# Connector.net
KiCad netlist of a schematic drawn in Altium Designer
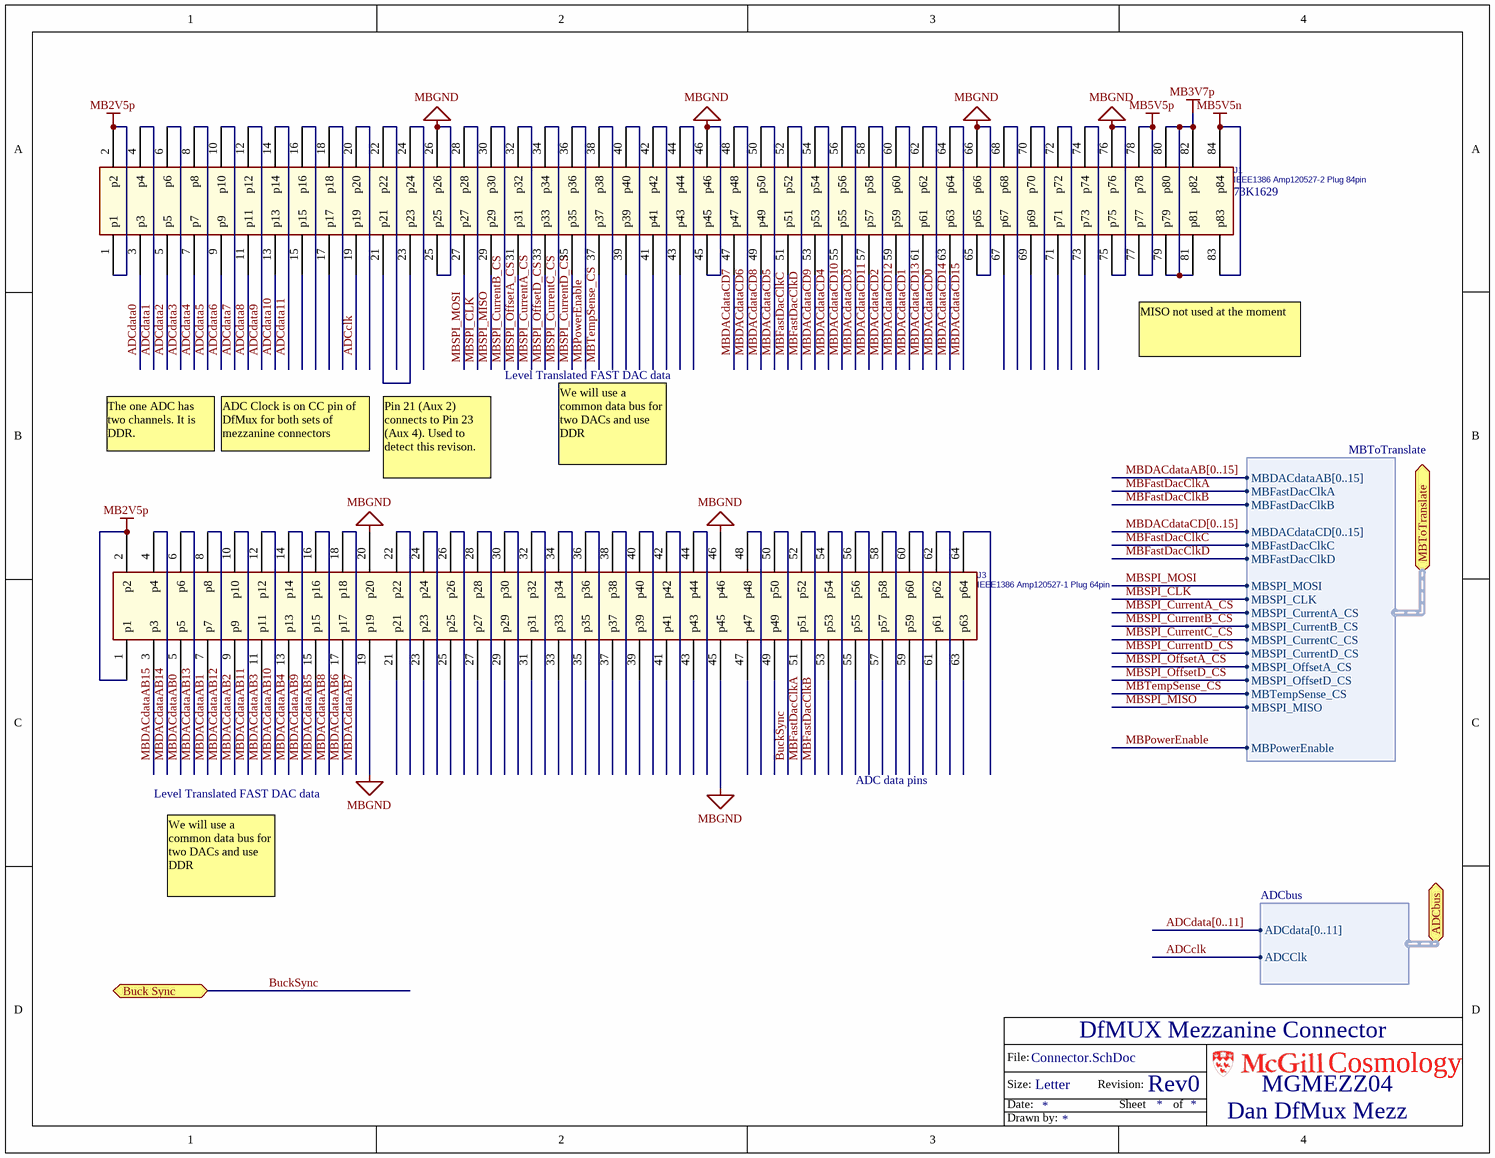
[diagram p0: Connector.SchDoc]

(export (version "E")
  (design (tool "Eeschema 10.0.6"))
  (components
    (comp (ref "J1")
      (value "IEEE1386 Amp120527-2 Plug 84pin")
      (fields
        (field (name "MANUFACTURER") "TE CONNECTIVITY / AMP")
        (field (name "SUPPLIER PART NUMBER 1") "73K1629")
        (field (name "MANUFACTURERS PART NUMBER") "5120527-2")
      )
      (libsource (lib "MGMEZZ04") (part "IEEE1386 Amp120527-2 Plug84pin"))
    )
    (comp (ref "J3")
      (value "IEEE1386 Amp120527-1 Plug 64pin")
      (fields
        (field (name "MANUFACTURER") "TE Connectivity")
        (field (name "MANUFACTURERS PART NUMBER") "120527-1")
      )
      (libsource (lib "MGMEZZ04") (part "IEEE1386 Amp120527-1 Plug 64pin"))
    )
  )
  (nets
    (net (code "4") (name "/ADCclk") (class "Default")
      (node (ref "J1") (pin "19") (pinfunction "p19_19") (pintype "passive"))
    )
    (net (code "5") (name "/ADCdata0") (class "Default")
      (node (ref "J1") (pin "3") (pinfunction "p3_3") (pintype "passive"))
    )
    (net (code "6") (name "/ADCdata1") (class "Default")
      (node (ref "J1") (pin "4") (pinfunction "p4_4") (pintype "passive"))
    )
    (net (code "7") (name "/ADCdata2") (class "Default")
      (node (ref "J1") (pin "5") (pinfunction "p5_5") (pintype "passive"))
    )
    (net (code "8") (name "/ADCdata3") (class "Default")
      (node (ref "J1") (pin "6") (pinfunction "p6_6") (pintype "passive"))
    )
    (net (code "9") (name "/ADCdata4") (class "Default")
      (node (ref "J1") (pin "7") (pinfunction "p7_7") (pintype "passive"))
    )
    (net (code "10") (name "/ADCdata5") (class "Default")
      (node (ref "J1") (pin "8") (pinfunction "p8_8") (pintype "passive"))
    )
    (net (code "11") (name "/ADCdata6") (class "Default")
      (node (ref "J1") (pin "9") (pinfunction "p9_9") (pintype "passive"))
    )
    (net (code "12") (name "/ADCdata7") (class "Default")
      (node (ref "J1") (pin "10") (pinfunction "p10_10") (pintype "passive"))
    )
    (net (code "13") (name "/ADCdata8") (class "Default")
      (node (ref "J1") (pin "11") (pinfunction "p11_11") (pintype "passive"))
    )
    (net (code "14") (name "/ADCdata9") (class "Default")
      (node (ref "J1") (pin "12") (pinfunction "p12_12") (pintype "passive"))
    )
    (net (code "15") (name "/ADCdata10") (class "Default")
      (node (ref "J1") (pin "13") (pinfunction "p13_13") (pintype "passive"))
    )
    (net (code "16") (name "/ADCdata11") (class "Default")
      (node (ref "J1") (pin "14") (pinfunction "p14_14") (pintype "passive"))
    )
    (net (code "17") (name "/BuckSync") (class "Default")
      (node (ref "J3") (pin "50") (pinfunction "p50_50") (pintype "passive"))
    )
    (net (code "18") (name "/MBDACdataAB0") (class "Default")
      (node (ref "J3") (pin "5") (pinfunction "p5_5") (pintype "passive"))
    )
    (net (code "19") (name "/MBDACdataAB1") (class "Default")
      (node (ref "J3") (pin "7") (pinfunction "p7_7") (pintype "passive"))
    )
    (net (code "20") (name "/MBDACdataAB2") (class "Default")
      (node (ref "J3") (pin "9") (pinfunction "p9_9") (pintype "passive"))
    )
    (net (code "21") (name "/MBDACdataAB3") (class "Default")
      (node (ref "J3") (pin "11") (pinfunction "p11_11") (pintype "passive"))
    )
    (net (code "22") (name "/MBDACdataAB4") (class "Default")
      (node (ref "J3") (pin "13") (pinfunction "p13_13") (pintype "passive"))
    )
    (net (code "23") (name "/MBDACdataAB5") (class "Default")
      (node (ref "J3") (pin "15") (pinfunction "p15_15") (pintype "passive"))
    )
    (net (code "24") (name "/MBDACdataAB6") (class "Default")
      (node (ref "J3") (pin "17") (pinfunction "p17_17") (pintype "passive"))
    )
    (net (code "25") (name "/MBDACdataAB7") (class "Default")
      (node (ref "J3") (pin "18") (pinfunction "p18_18") (pintype "passive"))
    )
    (net (code "26") (name "/MBDACdataAB8") (class "Default")
      (node (ref "J3") (pin "16") (pinfunction "p16_16") (pintype "passive"))
    )
    (net (code "27") (name "/MBDACdataAB9") (class "Default")
      (node (ref "J3") (pin "14") (pinfunction "p14_14") (pintype "passive"))
    )
    (net (code "28") (name "/MBDACdataAB10") (class "Default")
      (node (ref "J3") (pin "12") (pinfunction "p12_12") (pintype "passive"))
    )
    (net (code "29") (name "/MBDACdataAB11") (class "Default")
      (node (ref "J3") (pin "10") (pinfunction "p10_10") (pintype "passive"))
    )
    (net (code "30") (name "/MBDACdataAB12") (class "Default")
      (node (ref "J3") (pin "8") (pinfunction "p8_8") (pintype "passive"))
    )
    (net (code "31") (name "/MBDACdataAB13") (class "Default")
      (node (ref "J3") (pin "6") (pinfunction "p6_6") (pintype "passive"))
    )
    (net (code "32") (name "/MBDACdataAB14") (class "Default")
      (node (ref "J3") (pin "4") (pinfunction "p4_4") (pintype "passive"))
    )
    (net (code "33") (name "/MBDACdataAB15") (class "Default")
      (node (ref "J3") (pin "3") (pinfunction "p3_3") (pintype "passive"))
    )
    (net (code "35") (name "/MBDACdataCD0") (class "Default")
      (node (ref "J1") (pin "62") (pinfunction "p62_62") (pintype "passive"))
    )
    (net (code "36") (name "/MBDACdataCD1") (class "Default")
      (node (ref "J1") (pin "60") (pinfunction "p60_60") (pintype "passive"))
    )
    (net (code "37") (name "/MBDACdataCD2") (class "Default")
      (node (ref "J1") (pin "58") (pinfunction "p58_58") (pintype "passive"))
    )
    (net (code "38") (name "/MBDACdataCD3") (class "Default")
      (node (ref "J1") (pin "56") (pinfunction "p56_56") (pintype "passive"))
    )
    (net (code "39") (name "/MBDACdataCD4") (class "Default")
      (node (ref "J1") (pin "54") (pinfunction "p54_54") (pintype "passive"))
    )
    (net (code "40") (name "/MBDACdataCD5") (class "Default")
      (node (ref "J1") (pin "50") (pinfunction "p50_50") (pintype "passive"))
    )
    (net (code "41") (name "/MBDACdataCD6") (class "Default")
      (node (ref "J1") (pin "48") (pinfunction "p48_48") (pintype "passive"))
    )
    (net (code "42") (name "/MBDACdataCD7") (class "Default")
      (node (ref "J1") (pin "47") (pinfunction "p47_47") (pintype "passive"))
    )
    (net (code "43") (name "/MBDACdataCD8") (class "Default")
      (node (ref "J1") (pin "49") (pinfunction "p49_49") (pintype "passive"))
    )
    (net (code "44") (name "/MBDACdataCD9") (class "Default")
      (node (ref "J1") (pin "53") (pinfunction "p53_53") (pintype "passive"))
    )
    (net (code "45") (name "/MBDACdataCD10") (class "Default")
      (node (ref "J1") (pin "55") (pinfunction "p55_55") (pintype "passive"))
    )
    (net (code "46") (name "/MBDACdataCD11") (class "Default")
      (node (ref "J1") (pin "57") (pinfunction "p57_57") (pintype "passive"))
    )
    (net (code "47") (name "/MBDACdataCD12") (class "Default")
      (node (ref "J1") (pin "59") (pinfunction "p59_59") (pintype "passive"))
    )
    (net (code "48") (name "/MBDACdataCD13") (class "Default")
      (node (ref "J1") (pin "61") (pinfunction "p61_61") (pintype "passive"))
    )
    (net (code "49") (name "/MBDACdataCD14") (class "Default")
      (node (ref "J1") (pin "63") (pinfunction "p63_63") (pintype "passive"))
    )
    (net (code "50") (name "/MBDACdataCD15") (class "Default")
      (node (ref "J1") (pin "64") (pinfunction "p64_64") (pintype "passive"))
    )
    (net (code "51") (name "/MBFastDacClkA") (class "Default")
      (node (ref "J3") (pin "51") (pinfunction "p51_51") (pintype "passive"))
    )
    (net (code "52") (name "/MBFastDacClkB") (class "Default")
      (node (ref "J3") (pin "52") (pinfunction "p52_52") (pintype "passive"))
    )
    (net (code "53") (name "/MBFastDacClkC") (class "Default")
      (node (ref "J1") (pin "51") (pinfunction "p51_51") (pintype "passive"))
    )
    (net (code "54") (name "/MBFastDacClkD") (class "Default")
      (node (ref "J1") (pin "52") (pinfunction "p52_52") (pintype "passive"))
    )
    (net (code "55") (name "/MBPowerEnable") (class "Default")
      (node (ref "J1") (pin "36") (pinfunction "p36_36") (pintype "passive"))
    )
    (net (code "56") (name "/MBSPI_CLK") (class "Default")
      (node (ref "J1") (pin "28") (pinfunction "p28_28") (pintype "passive"))
    )
    (net (code "57") (name "/MBSPI_CurrentA_CS") (class "Default")
      (node (ref "J1") (pin "32") (pinfunction "p32_32") (pintype "passive"))
    )
    (net (code "58") (name "/MBSPI_CurrentB_CS") (class "Default")
      (node (ref "J1") (pin "30") (pinfunction "p30_30") (pintype "passive"))
    )
    (net (code "59") (name "/MBSPI_CurrentC_CS") (class "Default")
      (node (ref "J1") (pin "34") (pinfunction "p34_34") (pintype "passive"))
    )
    (net (code "60") (name "/MBSPI_CurrentD_CS") (class "Default")
      (node (ref "J1") (pin "35") (pinfunction "p35_35") (pintype "passive"))
    )
    (net (code "61") (name "/MBSPI_MISO") (class "Default")
      (node (ref "J1") (pin "29") (pinfunction "p29_29") (pintype "passive"))
    )
    (net (code "62") (name "/MBSPI_MOSI") (class "Default")
      (node (ref "J1") (pin "27") (pinfunction "p27_27") (pintype "passive"))
    )
    (net (code "63") (name "/MBSPI_OffsetA_CS") (class "Default")
      (node (ref "J1") (pin "31") (pinfunction "p31_31") (pintype "passive"))
    )
    (net (code "64") (name "/MBSPI_OffsetD_CS") (class "Default")
      (node (ref "J1") (pin "33") (pinfunction "p33_33") (pintype "passive"))
    )
    (net (code "65") (name "/MBTempSense_CS") (class "Default")
      (node (ref "J1") (pin "37") (pinfunction "p37_37") (pintype "passive"))
    )
    (net (code "69") (name "MB2V5p") (class "Default")
      (node (ref "J1") (pin "1") (pinfunction "p1_1") (pintype "passive"))
      (node (ref "J1") (pin "2") (pinfunction "p2_2") (pintype "passive"))
      (node (ref "J3") (pin "1") (pinfunction "p1_1") (pintype "passive"))
      (node (ref "J3") (pin "2") (pinfunction "p2_2") (pintype "passive"))
    )
    (net (code "70") (name "MB3V7p") (class "Default")
      (node (ref "J1") (pin "79") (pinfunction "p79_79") (pintype "passive"))
      (node (ref "J1") (pin "80") (pinfunction "p80_80") (pintype "passive"))
      (node (ref "J1") (pin "81") (pinfunction "p81_81") (pintype "passive"))
      (node (ref "J1") (pin "82") (pinfunction "p82_82") (pintype "passive"))
    )
    (net (code "71") (name "MB5V5n") (class "Default")
      (node (ref "J1") (pin "83") (pinfunction "p83_83") (pintype "passive"))
      (node (ref "J1") (pin "84") (pinfunction "p84_84") (pintype "passive"))
    )
    (net (code "72") (name "MB5V5p") (class "Default")
      (node (ref "J1") (pin "77") (pinfunction "p77_77") (pintype "passive"))
      (node (ref "J1") (pin "78") (pinfunction "p78_78") (pintype "passive"))
    )
    (net (code "73") (name "MBGND") (class "Default")
      (node (ref "J1") (pin "25") (pinfunction "p25_25") (pintype "passive"))
      (node (ref "J1") (pin "26") (pinfunction "p26_26") (pintype "passive"))
      (node (ref "J1") (pin "45") (pinfunction "p45_45") (pintype "passive"))
      (node (ref "J1") (pin "46") (pinfunction "p46_46") (pintype "passive"))
      (node (ref "J1") (pin "65") (pinfunction "p65_65") (pintype "passive"))
      (node (ref "J1") (pin "66") (pinfunction "p66_66") (pintype "passive"))
      (node (ref "J1") (pin "75") (pinfunction "p75_75") (pintype "passive"))
      (node (ref "J1") (pin "76") (pinfunction "p76_76") (pintype "passive"))
      (node (ref "J3") (pin "19") (pinfunction "p19_19") (pintype "passive"))
      (node (ref "J3") (pin "20") (pinfunction "p20_20") (pintype "passive"))
      (node (ref "J3") (pin "45") (pinfunction "p45_45") (pintype "passive"))
      (node (ref "J3") (pin "46") (pinfunction "p46_46") (pintype "passive"))
    )
    (net (code "74") (name "Net-(J1-p21)") (class "Default")
      (node (ref "J1") (pin "21") (pinfunction "p21_21") (pintype "passive"))
      (node (ref "J1") (pin "23") (pinfunction "p23_23") (pintype "passive"))
    )
    (net (code "75") (name "unconnected-(J1-p15-Pad15)") (class "Default")
      (node (ref "J1") (pin "15") (pinfunction "p15_15") (pintype "passive"))
    )
    (net (code "76") (name "unconnected-(J1-p16-Pad16)") (class "Default")
      (node (ref "J1") (pin "16") (pinfunction "p16_16") (pintype "passive"))
    )
    (net (code "77") (name "unconnected-(J1-p17-Pad17)") (class "Default")
      (node (ref "J1") (pin "17") (pinfunction "p17_17") (pintype "passive"))
    )
    (net (code "78") (name "unconnected-(J1-p18-Pad18)") (class "Default")
      (node (ref "J1") (pin "18") (pinfunction "p18_18") (pintype "passive"))
    )
    (net (code "79") (name "unconnected-(J1-p20-Pad20)") (class "Default")
      (node (ref "J1") (pin "20") (pinfunction "p20_20") (pintype "passive"))
    )
    (net (code "80") (name "unconnected-(J1-p22-Pad22)") (class "Default")
      (node (ref "J1") (pin "22") (pinfunction "p22_22") (pintype "passive"))
    )
    (net (code "81") (name "unconnected-(J1-p24-Pad24)") (class "Default")
      (node (ref "J1") (pin "24") (pinfunction "p24_24") (pintype "passive"))
    )
    (net (code "82") (name "unconnected-(J1-p38-Pad38)") (class "Default")
      (node (ref "J1") (pin "38") (pinfunction "p38_38") (pintype "passive"))
    )
    (net (code "83") (name "unconnected-(J1-p39-Pad39)") (class "Default")
      (node (ref "J1") (pin "39") (pinfunction "p39_39") (pintype "passive"))
    )
    (net (code "84") (name "unconnected-(J1-p40-Pad40)") (class "Default")
      (node (ref "J1") (pin "40") (pinfunction "p40_40") (pintype "passive"))
    )
    (net (code "85") (name "unconnected-(J1-p41-Pad41)") (class "Default")
      (node (ref "J1") (pin "41") (pinfunction "p41_41") (pintype "passive"))
    )
    (net (code "86") (name "unconnected-(J1-p42-Pad42)") (class "Default")
      (node (ref "J1") (pin "42") (pinfunction "p42_42") (pintype "passive"))
    )
    (net (code "87") (name "unconnected-(J1-p43-Pad43)") (class "Default")
      (node (ref "J1") (pin "43") (pinfunction "p43_43") (pintype "passive"))
    )
    (net (code "88") (name "unconnected-(J1-p44-Pad44)") (class "Default")
      (node (ref "J1") (pin "44") (pinfunction "p44_44") (pintype "passive"))
    )
    (net (code "89") (name "unconnected-(J1-p67-Pad67)") (class "Default")
      (node (ref "J1") (pin "67") (pinfunction "p67_67") (pintype "passive"))
    )
    (net (code "90") (name "unconnected-(J1-p68-Pad68)") (class "Default")
      (node (ref "J1") (pin "68") (pinfunction "p68_68") (pintype "passive"))
    )
    (net (code "91") (name "unconnected-(J1-p69-Pad69)") (class "Default")
      (node (ref "J1") (pin "69") (pinfunction "p69_69") (pintype "passive"))
    )
    (net (code "92") (name "unconnected-(J1-p70-Pad70)") (class "Default")
      (node (ref "J1") (pin "70") (pinfunction "p70_70") (pintype "passive"))
    )
    (net (code "93") (name "unconnected-(J1-p71-Pad71)") (class "Default")
      (node (ref "J1") (pin "71") (pinfunction "p71_71") (pintype "passive"))
    )
    (net (code "94") (name "unconnected-(J1-p72-Pad72)") (class "Default")
      (node (ref "J1") (pin "72") (pinfunction "p72_72") (pintype "passive"))
    )
    (net (code "95") (name "unconnected-(J1-p73-Pad73)") (class "Default")
      (node (ref "J1") (pin "73") (pinfunction "p73_73") (pintype "passive"))
    )
    (net (code "96") (name "unconnected-(J1-p74-Pad74)") (class "Default")
      (node (ref "J1") (pin "74") (pinfunction "p74_74") (pintype "passive"))
    )
    (net (code "97") (name "unconnected-(J3-p21-Pad21)") (class "Default")
      (node (ref "J3") (pin "21") (pinfunction "p21_21") (pintype "passive"))
    )
    (net (code "98") (name "unconnected-(J3-p22-Pad22)") (class "Default")
      (node (ref "J3") (pin "22") (pinfunction "p22_22") (pintype "passive"))
    )
    (net (code "99") (name "unconnected-(J3-p23-Pad23)") (class "Default")
      (node (ref "J3") (pin "23") (pinfunction "p23_23") (pintype "passive"))
    )
    (net (code "100") (name "unconnected-(J3-p24-Pad24)") (class "Default")
      (node (ref "J3") (pin "24") (pinfunction "p24_24") (pintype "passive"))
    )
    (net (code "101") (name "unconnected-(J3-p25-Pad25)") (class "Default")
      (node (ref "J3") (pin "25") (pinfunction "p25_25") (pintype "passive"))
    )
    (net (code "102") (name "unconnected-(J3-p26-Pad26)") (class "Default")
      (node (ref "J3") (pin "26") (pinfunction "p26_26") (pintype "passive"))
    )
    (net (code "103") (name "unconnected-(J3-p27-Pad27)") (class "Default")
      (node (ref "J3") (pin "27") (pinfunction "p27_27") (pintype "passive"))
    )
    (net (code "104") (name "unconnected-(J3-p28-Pad28)") (class "Default")
      (node (ref "J3") (pin "28") (pinfunction "p28_28") (pintype "passive"))
    )
    (net (code "105") (name "unconnected-(J3-p29-Pad29)") (class "Default")
      (node (ref "J3") (pin "29") (pinfunction "p29_29") (pintype "passive"))
    )
    (net (code "106") (name "unconnected-(J3-p30-Pad30)") (class "Default")
      (node (ref "J3") (pin "30") (pinfunction "p30_30") (pintype "passive"))
    )
    (net (code "107") (name "unconnected-(J3-p31-Pad31)") (class "Default")
      (node (ref "J3") (pin "31") (pinfunction "p31_31") (pintype "passive"))
    )
    (net (code "108") (name "unconnected-(J3-p32-Pad32)") (class "Default")
      (node (ref "J3") (pin "32") (pinfunction "p32_32") (pintype "passive"))
    )
    (net (code "109") (name "unconnected-(J3-p33-Pad33)") (class "Default")
      (node (ref "J3") (pin "33") (pinfunction "p33_33") (pintype "passive"))
    )
    (net (code "110") (name "unconnected-(J3-p34-Pad34)") (class "Default")
      (node (ref "J3") (pin "34") (pinfunction "p34_34") (pintype "passive"))
    )
    (net (code "111") (name "unconnected-(J3-p35-Pad35)") (class "Default")
      (node (ref "J3") (pin "35") (pinfunction "p35_35") (pintype "passive"))
    )
    (net (code "112") (name "unconnected-(J3-p36-Pad36)") (class "Default")
      (node (ref "J3") (pin "36") (pinfunction "p36_36") (pintype "passive"))
    )
    (net (code "113") (name "unconnected-(J3-p37-Pad37)") (class "Default")
      (node (ref "J3") (pin "37") (pinfunction "p37_37") (pintype "passive"))
    )
    (net (code "114") (name "unconnected-(J3-p38-Pad38)") (class "Default")
      (node (ref "J3") (pin "38") (pinfunction "p38_38") (pintype "passive"))
    )
    (net (code "115") (name "unconnected-(J3-p39-Pad39)") (class "Default")
      (node (ref "J3") (pin "39") (pinfunction "p39_39") (pintype "passive"))
    )
    (net (code "116") (name "unconnected-(J3-p40-Pad40)") (class "Default")
      (node (ref "J3") (pin "40") (pinfunction "p40_40") (pintype "passive"))
    )
    (net (code "117") (name "unconnected-(J3-p41-Pad41)") (class "Default")
      (node (ref "J3") (pin "41") (pinfunction "p41_41") (pintype "passive"))
    )
    (net (code "118") (name "unconnected-(J3-p42-Pad42)") (class "Default")
      (node (ref "J3") (pin "42") (pinfunction "p42_42") (pintype "passive"))
    )
    (net (code "119") (name "unconnected-(J3-p43-Pad43)") (class "Default")
      (node (ref "J3") (pin "43") (pinfunction "p43_43") (pintype "passive"))
    )
    (net (code "120") (name "unconnected-(J3-p44-Pad44)") (class "Default")
      (node (ref "J3") (pin "44") (pinfunction "p44_44") (pintype "passive"))
    )
    (net (code "121") (name "unconnected-(J3-p47-Pad47)") (class "Default")
      (node (ref "J3") (pin "47") (pinfunction "p47_47") (pintype "passive"))
    )
    (net (code "122") (name "unconnected-(J3-p48-Pad48)") (class "Default")
      (node (ref "J3") (pin "48") (pinfunction "p48_48") (pintype "passive"))
    )
    (net (code "123") (name "unconnected-(J3-p49-Pad49)") (class "Default")
      (node (ref "J3") (pin "49") (pinfunction "p49_49") (pintype "passive"))
    )
    (net (code "124") (name "unconnected-(J3-p53-Pad53)") (class "Default")
      (node (ref "J3") (pin "53") (pinfunction "p53_53") (pintype "passive"))
    )
    (net (code "125") (name "unconnected-(J3-p54-Pad54)") (class "Default")
      (node (ref "J3") (pin "54") (pinfunction "p54_54") (pintype "passive"))
    )
    (net (code "126") (name "unconnected-(J3-p55-Pad55)") (class "Default")
      (node (ref "J3") (pin "55") (pinfunction "p55_55") (pintype "passive"))
    )
    (net (code "127") (name "unconnected-(J3-p56-Pad56)") (class "Default")
      (node (ref "J3") (pin "56") (pinfunction "p56_56") (pintype "passive"))
    )
    (net (code "128") (name "unconnected-(J3-p57-Pad57)") (class "Default")
      (node (ref "J3") (pin "57") (pinfunction "p57_57") (pintype "passive"))
    )
    (net (code "129") (name "unconnected-(J3-p58-Pad58)") (class "Default")
      (node (ref "J3") (pin "58") (pinfunction "p58_58") (pintype "passive"))
    )
    (net (code "130") (name "unconnected-(J3-p59-Pad59)") (class "Default")
      (node (ref "J3") (pin "59") (pinfunction "p59_59") (pintype "passive"))
    )
    (net (code "131") (name "unconnected-(J3-p60-Pad60)") (class "Default")
      (node (ref "J3") (pin "60") (pinfunction "p60_60") (pintype "passive"))
    )
    (net (code "132") (name "unconnected-(J3-p61-Pad61)") (class "Default")
      (node (ref "J3") (pin "61") (pinfunction "p61_61") (pintype "passive"))
    )
    (net (code "133") (name "unconnected-(J3-p62-Pad62)") (class "Default")
      (node (ref "J3") (pin "62") (pinfunction "p62_62") (pintype "passive"))
    )
    (net (code "134") (name "unconnected-(J3-p63-Pad63)") (class "Default")
      (node (ref "J3") (pin "63") (pinfunction "p63_63") (pintype "passive"))
    )
    (net (code "135") (name "unconnected-(J3-p64-Pad64)") (class "Default")
      (node (ref "J3") (pin "64") (pinfunction "p64_64") (pintype "passive"))
    )
  )
)
